# Group_12.net
KiCad netlist of a schematic drawn in EAGLE
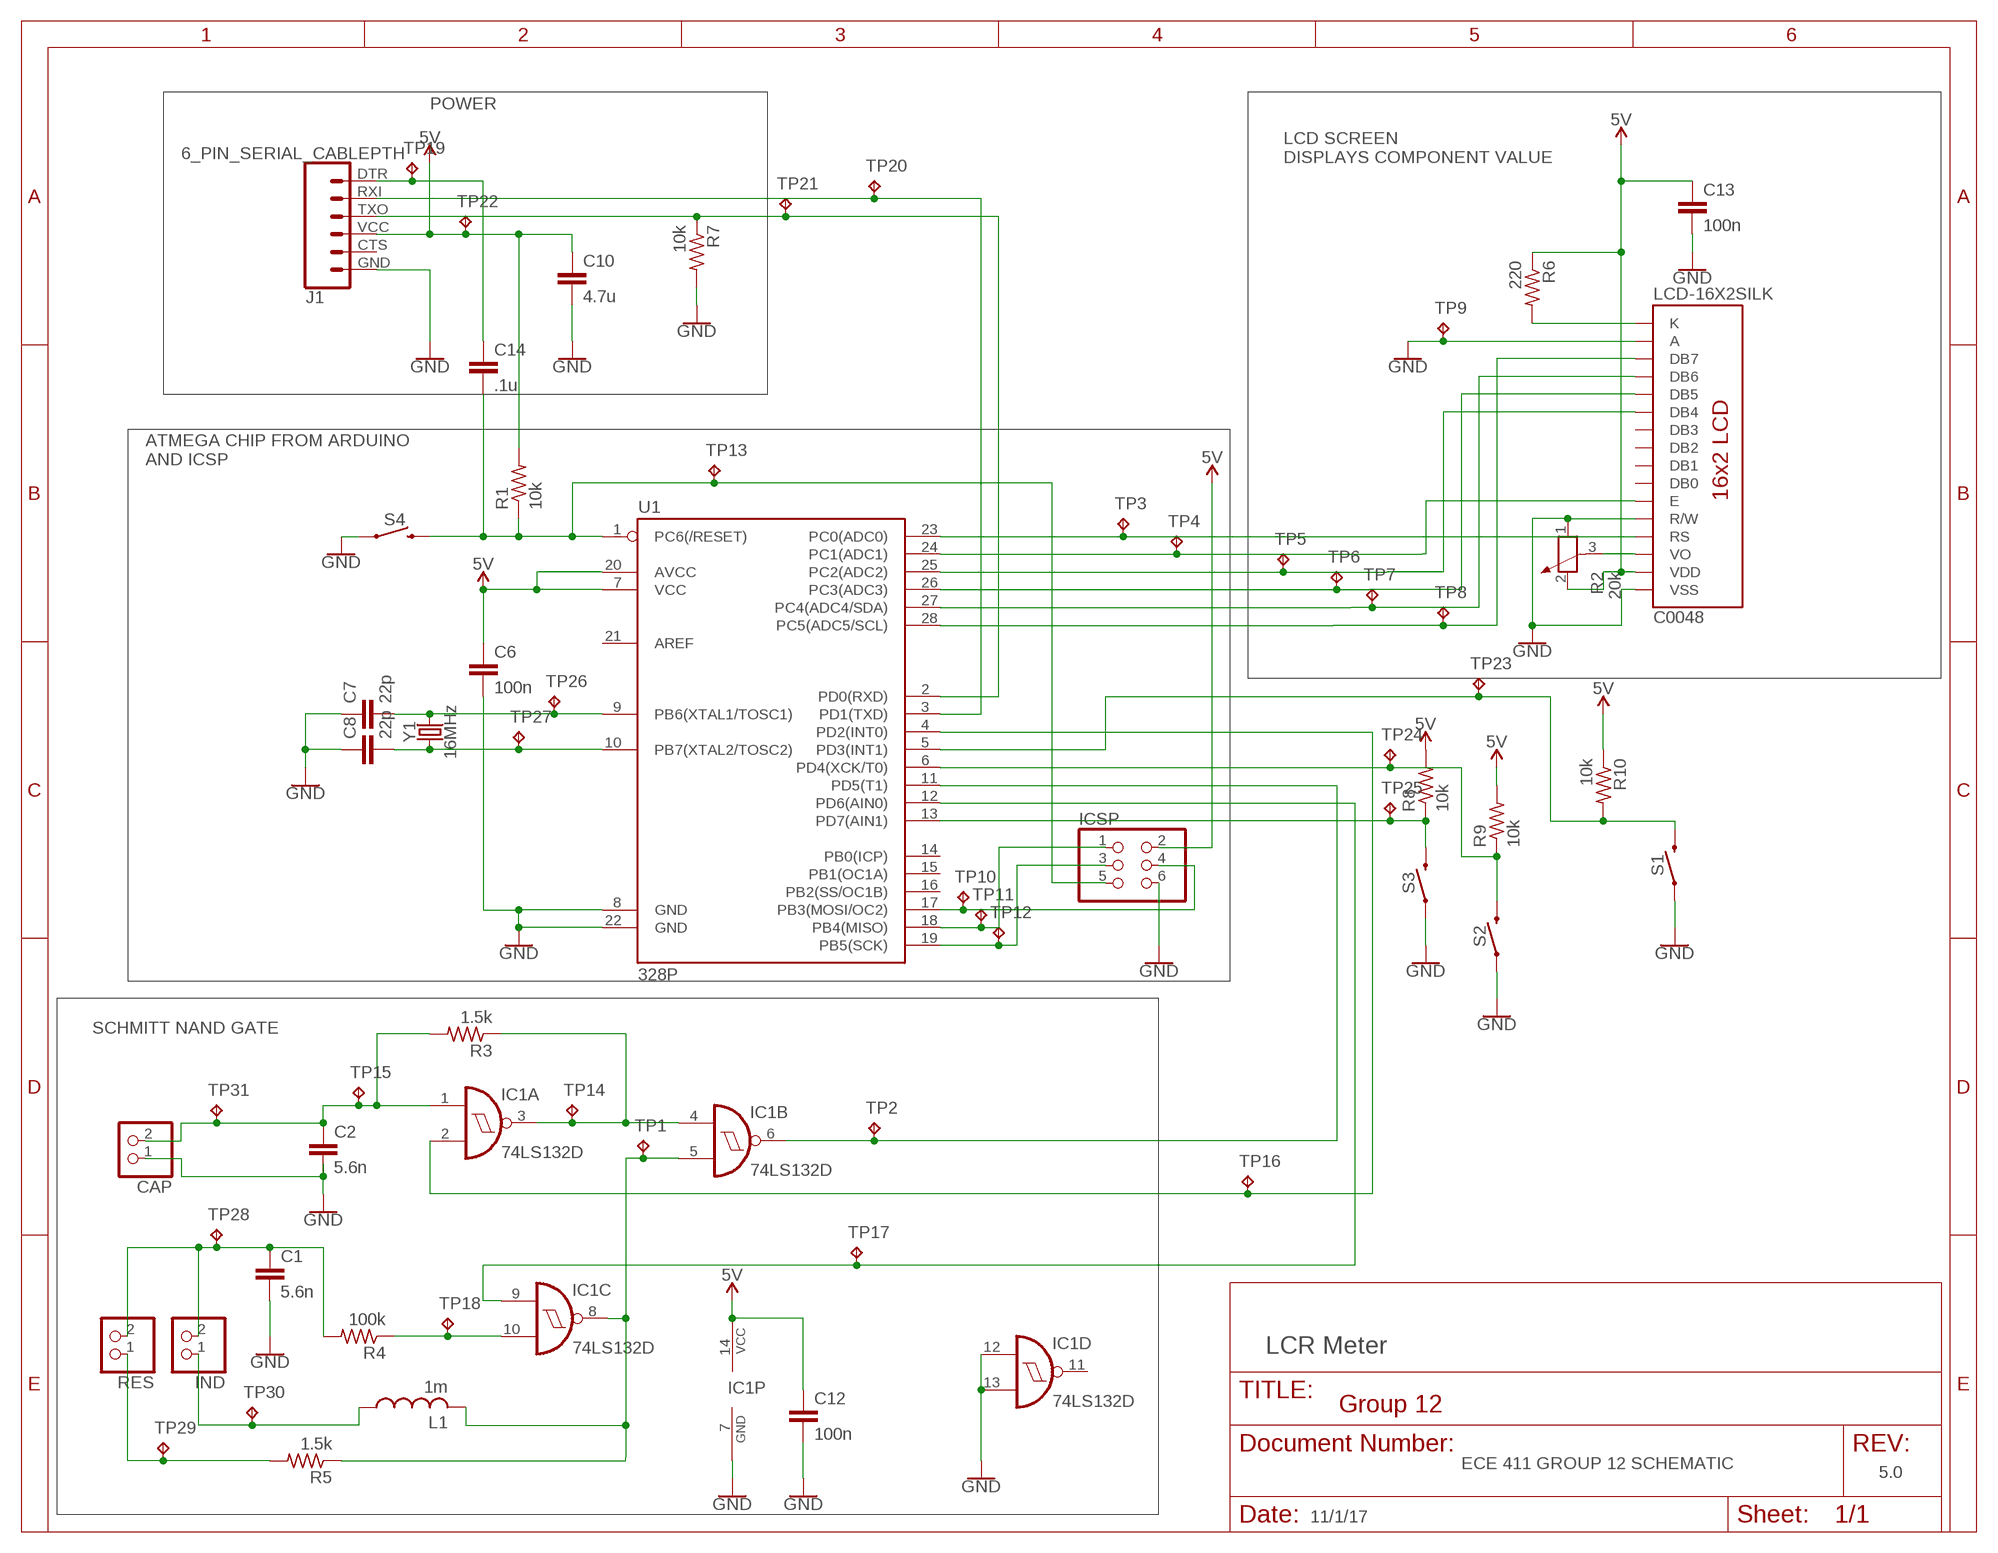
[diagram p0: schematic, sheet 1]

(export (version "E")
  (design (tool "Eeschema 10.0.6"))
  (components
    (comp (ref "C1")
      (value "5.6n")
      (footprint "eagle-import:C0805K")
      (libsource (lib "eagle-import") (part "C-EUC0805K"))
    )
    (comp (ref "C2")
      (value "5.6n")
      (footprint "eagle-import:C0805K")
      (libsource (lib "eagle-import") (part "C-EUC0805K"))
    )
    (comp (ref "C6")
      (value "100n")
      (footprint "eagle-import:C0805K")
      (libsource (lib "eagle-import") (part "C-EUC0805K"))
    )
    (comp (ref "C7")
      (value "22p")
      (footprint "eagle-import:C0805K")
      (libsource (lib "eagle-import") (part "C-EUC0805K"))
    )
    (comp (ref "C8")
      (value "22p")
      (footprint "eagle-import:C0805K")
      (libsource (lib "eagle-import") (part "C-EUC0805K"))
    )
    (comp (ref "C10")
      (value "4.7u")
      (footprint "eagle-import:C0805K")
      (libsource (lib "eagle-import") (part "C-EUC0805K"))
    )
    (comp (ref "C12")
      (value "100n")
      (footprint "eagle-import:C0805K")
      (libsource (lib "eagle-import") (part "C-EUC0805K"))
    )
    (comp (ref "C13")
      (value "100n")
      (footprint "eagle-import:C0805K")
      (libsource (lib "eagle-import") (part "C-EUC0805K"))
    )
    (comp (ref "C14")
      (value ".1u")
      (footprint "eagle-import:C0805K")
      (libsource (lib "eagle-import") (part "C-EUC0805K"))
    )
    (comp (ref "C0048")
      (value "LCD-16X2SILK")
      (footprint "eagle-import:LCD-16X2")
      (libsource (lib "eagle-import") (part "LCD-16X2SILK"))
    )
    (comp (ref "CAP")
      (value "PINHD-1X2")
      (footprint "eagle-import:1X02")
      (libsource (lib "eagle-import") (part "PINHD-1X2"))
    )
    (comp (ref "IC1")
      (value "74LS132D")
      (footprint "eagle-import:SO14")
      (libsource (lib "eagle-import") (part "74132DLS"))
    )
    (comp (ref "ICSP")
      (value "PINHD-2X3")
      (footprint "eagle-import:2X03")
      (libsource (lib "eagle-import") (part "PINHD-2X3"))
    )
    (comp (ref "IND")
      (value "PINHD-1X2")
      (footprint "eagle-import:1X02")
      (libsource (lib "eagle-import") (part "PINHD-1X2"))
    )
    (comp (ref "J1")
      (value "6_PIN_SERIAL_CABLEPTH")
      (footprint "eagle-import:FTDI_BASIC")
      (libsource (lib "eagle-import") (part "6_PIN_SERIAL_CABLEPTH"))
    )
    (comp (ref "L1")
      (value "1m")
      (footprint "eagle-import:0204_5")
      (libsource (lib "eagle-import") (part "L-US0204/5"))
    )
    (comp (ref "R1")
      (value "10k")
      (footprint "eagle-import:R0805")
      (libsource (lib "eagle-import") (part "R-US_R0805"))
    )
    (comp (ref "R2")
      (value "20k")
      (footprint "eagle-import:PT-10")
      (libsource (lib "eagle-import") (part "POTENTIOMETER_PT-10"))
    )
    (comp (ref "R3")
      (value "1.5k")
      (footprint "eagle-import:M0805")
      (libsource (lib "eagle-import") (part "R-US_M0805"))
    )
    (comp (ref "R4")
      (value "100k")
      (footprint "eagle-import:M0805")
      (libsource (lib "eagle-import") (part "R-US_M0805"))
    )
    (comp (ref "R5")
      (value "1.5k")
      (footprint "eagle-import:M0805")
      (libsource (lib "eagle-import") (part "R-US_M0805"))
    )
    (comp (ref "R6")
      (value "220")
      (footprint "eagle-import:R0805")
      (libsource (lib "eagle-import") (part "R-US_R0805"))
    )
    (comp (ref "R7")
      (value "10k")
      (footprint "eagle-import:R0805")
      (libsource (lib "eagle-import") (part "R-US_R0805"))
    )
    (comp (ref "R8")
      (value "10k")
      (footprint "eagle-import:R0805")
      (libsource (lib "eagle-import") (part "R-US_R0805"))
    )
    (comp (ref "R9")
      (value "10k")
      (footprint "eagle-import:R0805")
      (libsource (lib "eagle-import") (part "R-US_R0805"))
    )
    (comp (ref "R10")
      (value "10k")
      (footprint "eagle-import:R0805")
      (libsource (lib "eagle-import") (part "R-US_R0805"))
    )
    (comp (ref "RES")
      (value "PINHD-1X2")
      (footprint "eagle-import:1X02")
      (libsource (lib "eagle-import") (part "PINHD-1X2"))
    )
    (comp (ref "S1")
      (value "MOMENTARY-SWITCH-SPST-SMD-6.0X3.5MM")
      (footprint "eagle-import:TACTILE_SWITCH_SMD_6.0X3.5MM")
      (libsource (lib "eagle-import") (part "MOMENTARY-SWITCH-SPST-SMD-6.0X3.5MM"))
    )
    (comp (ref "S2")
      (value "MOMENTARY-SWITCH-SPST-SMD-6.0X3.5MM")
      (footprint "eagle-import:TACTILE_SWITCH_SMD_6.0X3.5MM")
      (libsource (lib "eagle-import") (part "MOMENTARY-SWITCH-SPST-SMD-6.0X3.5MM"))
    )
    (comp (ref "S3")
      (value "MOMENTARY-SWITCH-SPST-SMD-6.0X3.5MM")
      (footprint "eagle-import:TACTILE_SWITCH_SMD_6.0X3.5MM")
      (libsource (lib "eagle-import") (part "MOMENTARY-SWITCH-SPST-SMD-6.0X3.5MM"))
    )
    (comp (ref "S4")
      (value "MOMENTARY-SWITCH-SPST-SMD-6.0X3.5MM")
      (footprint "eagle-import:TACTILE_SWITCH_SMD_6.0X3.5MM")
      (libsource (lib "eagle-import") (part "MOMENTARY-SWITCH-SPST-SMD-6.0X3.5MM"))
    )
    (comp (ref "TP1")
      (value "TPPAD1-13")
      (footprint "eagle-import:P1-13")
      (libsource (lib "eagle-import") (part "TPPAD1-13"))
    )
    (comp (ref "TP2")
      (value "TPPAD1-13")
      (footprint "eagle-import:P1-13")
      (libsource (lib "eagle-import") (part "TPPAD1-13"))
    )
    (comp (ref "TP3")
      (value "TPPAD1-13")
      (footprint "eagle-import:P1-13")
      (libsource (lib "eagle-import") (part "TPPAD1-13"))
    )
    (comp (ref "TP4")
      (value "TPPAD1-13")
      (footprint "eagle-import:P1-13")
      (libsource (lib "eagle-import") (part "TPPAD1-13"))
    )
    (comp (ref "TP5")
      (value "TPPAD1-13")
      (footprint "eagle-import:P1-13")
      (libsource (lib "eagle-import") (part "TPPAD1-13"))
    )
    (comp (ref "TP6")
      (value "TPPAD1-13")
      (footprint "eagle-import:P1-13")
      (libsource (lib "eagle-import") (part "TPPAD1-13"))
    )
    (comp (ref "TP7")
      (value "TPPAD1-13")
      (footprint "eagle-import:P1-13")
      (libsource (lib "eagle-import") (part "TPPAD1-13"))
    )
    (comp (ref "TP8")
      (value "TPPAD1-13")
      (footprint "eagle-import:P1-13")
      (libsource (lib "eagle-import") (part "TPPAD1-13"))
    )
    (comp (ref "TP9")
      (value "TPPAD1-13")
      (footprint "eagle-import:P1-13")
      (libsource (lib "eagle-import") (part "TPPAD1-13"))
    )
    (comp (ref "TP10")
      (value "TPPAD1-13")
      (footprint "eagle-import:P1-13")
      (libsource (lib "eagle-import") (part "TPPAD1-13"))
    )
    (comp (ref "TP11")
      (value "TPPAD1-13")
      (footprint "eagle-import:P1-13")
      (libsource (lib "eagle-import") (part "TPPAD1-13"))
    )
    (comp (ref "TP12")
      (value "TPPAD1-13")
      (footprint "eagle-import:P1-13")
      (libsource (lib "eagle-import") (part "TPPAD1-13"))
    )
    (comp (ref "TP13")
      (value "TPPAD1-13")
      (footprint "eagle-import:P1-13")
      (libsource (lib "eagle-import") (part "TPPAD1-13"))
    )
    (comp (ref "TP14")
      (value "TPPAD1-13")
      (footprint "eagle-import:P1-13")
      (libsource (lib "eagle-import") (part "TPPAD1-13"))
    )
    (comp (ref "TP15")
      (value "TPPAD1-13")
      (footprint "eagle-import:P1-13")
      (libsource (lib "eagle-import") (part "TPPAD1-13"))
    )
    (comp (ref "TP16")
      (value "TPPAD1-13")
      (footprint "eagle-import:P1-13")
      (libsource (lib "eagle-import") (part "TPPAD1-13"))
    )
    (comp (ref "TP17")
      (value "TPPAD1-13")
      (footprint "eagle-import:P1-13")
      (libsource (lib "eagle-import") (part "TPPAD1-13"))
    )
    (comp (ref "TP18")
      (value "TPPAD1-13")
      (footprint "eagle-import:P1-13")
      (libsource (lib "eagle-import") (part "TPPAD1-13"))
    )
    (comp (ref "TP19")
      (value "TPPAD1-13")
      (footprint "eagle-import:P1-13")
      (libsource (lib "eagle-import") (part "TPPAD1-13"))
    )
    (comp (ref "TP20")
      (value "TPPAD1-13")
      (footprint "eagle-import:P1-13")
      (libsource (lib "eagle-import") (part "TPPAD1-13"))
    )
    (comp (ref "TP21")
      (value "TPPAD1-13")
      (footprint "eagle-import:P1-13")
      (libsource (lib "eagle-import") (part "TPPAD1-13"))
    )
    (comp (ref "TP22")
      (value "TPPAD1-13")
      (footprint "eagle-import:P1-13")
      (libsource (lib "eagle-import") (part "TPPAD1-13"))
    )
    (comp (ref "TP23")
      (value "TPPAD1-13")
      (footprint "eagle-import:P1-13")
      (libsource (lib "eagle-import") (part "TPPAD1-13"))
    )
    (comp (ref "TP24")
      (value "TPPAD1-13")
      (footprint "eagle-import:P1-13")
      (libsource (lib "eagle-import") (part "TPPAD1-13"))
    )
    (comp (ref "TP25")
      (value "TPPAD1-13")
      (footprint "eagle-import:P1-13")
      (libsource (lib "eagle-import") (part "TPPAD1-13"))
    )
    (comp (ref "TP26")
      (value "TPPAD1-13")
      (footprint "eagle-import:P1-13")
      (libsource (lib "eagle-import") (part "TPPAD1-13"))
    )
    (comp (ref "TP27")
      (value "TPPAD1-13")
      (footprint "eagle-import:P1-13")
      (libsource (lib "eagle-import") (part "TPPAD1-13"))
    )
    (comp (ref "TP28")
      (value "TPPAD1-13")
      (footprint "eagle-import:P1-13")
      (libsource (lib "eagle-import") (part "TPPAD1-13"))
    )
    (comp (ref "TP29")
      (value "TPPAD1-13")
      (footprint "eagle-import:P1-13")
      (libsource (lib "eagle-import") (part "TPPAD1-13"))
    )
    (comp (ref "TP30")
      (value "TPPAD1-13")
      (footprint "eagle-import:P1-13")
      (libsource (lib "eagle-import") (part "TPPAD1-13"))
    )
    (comp (ref "TP31")
      (value "TPPAD1-13")
      (footprint "eagle-import:P1-13")
      (libsource (lib "eagle-import") (part "TPPAD1-13"))
    )
    (comp (ref "U1")
      (value "328P")
      (footprint "eagle-import:DIP28")
      (libsource (lib "eagle-import") (part "ATMEGA328P_PDIP"))
    )
    (comp (ref "Y1")
      (value "16MHz")
      (footprint "eagle-import:CRYSTAL-SMD-5X3.2-4PAD")
      (libsource (lib "eagle-import") (part "CRYSTAL-16MHZSMD-5X3.2"))
    )
  )
  (nets
    (net (code "1") (name "5V") (class "Default")
      (node (ref "C0048") (pin "2") (pinfunction "VDD_2") (pintype "power_in"))
      (node (ref "C10") (pin "1") (pinfunction "1_1") (pintype "passive"))
      (node (ref "C12") (pin "1") (pinfunction "1_1") (pintype "passive"))
      (node (ref "C13") (pin "1") (pinfunction "1_1") (pintype "passive"))
      (node (ref "C6") (pin "1") (pinfunction "1_1") (pintype "passive"))
      (node (ref "IC1") (pin "14") (pinfunction "VCC_14") (pintype "power_in"))
      (node (ref "ICSP") (pin "2") (pinfunction "2_2") (pintype "passive"))
      (node (ref "J1") (pin "VCC") (pinfunction "4_VCC") (pintype "passive"))
      (node (ref "R1") (pin "2") (pinfunction "2_2") (pintype "passive"))
      (node (ref "R10") (pin "1") (pinfunction "1_1") (pintype "passive"))
      (node (ref "R2") (pin "2") (pinfunction "2_2") (pintype "passive"))
      (node (ref "R6") (pin "1") (pinfunction "1_1") (pintype "passive"))
      (node (ref "R8") (pin "2") (pinfunction "2_2") (pintype "passive"))
      (node (ref "R9") (pin "2") (pinfunction "2_2") (pintype "passive"))
      (node (ref "TP22") (pin "TP") (pinfunction "TP_TP") (pintype "input"))
      (node (ref "U1") (pin "20") (pinfunction "AVCC_20") (pintype "bidirectional"))
      (node (ref "U1") (pin "7") (pinfunction "VCC_7") (pintype "bidirectional"))
    )
    (net (code "2") (name "GND") (class "Default")
      (node (ref "C0048") (pin "1") (pinfunction "VSS_1") (pintype "power_in"))
      (node (ref "C0048") (pin "15") (pinfunction "A_15") (pintype "power_in"))
      (node (ref "C0048") (pin "5") (pinfunction "R/W_5") (pintype "input"))
      (node (ref "C1") (pin "2") (pinfunction "2_2") (pintype "passive"))
      (node (ref "C10") (pin "2") (pinfunction "2_2") (pintype "passive"))
      (node (ref "C12") (pin "2") (pinfunction "2_2") (pintype "passive"))
      (node (ref "C13") (pin "2") (pinfunction "2_2") (pintype "passive"))
      (node (ref "C2") (pin "2") (pinfunction "2_2") (pintype "passive"))
      (node (ref "C6") (pin "2") (pinfunction "2_2") (pintype "passive"))
      (node (ref "C7") (pin "1") (pinfunction "1_1") (pintype "passive"))
      (node (ref "C8") (pin "1") (pinfunction "1_1") (pintype "passive"))
      (node (ref "CAP") (pin "1") (pinfunction "1_1") (pintype "passive"))
      (node (ref "IC1") (pin "12") (pinfunction "I0_12") (pintype "input"))
      (node (ref "IC1") (pin "13") (pinfunction "I1_13") (pintype "input"))
      (node (ref "IC1") (pin "7") (pinfunction "GND_7") (pintype "power_in"))
      (node (ref "ICSP") (pin "6") (pinfunction "6_6") (pintype "passive"))
      (node (ref "J1") (pin "GND") (pinfunction "6_GND") (pintype "passive"))
      (node (ref "R2") (pin "1") (pinfunction "1_1") (pintype "passive"))
      (node (ref "R7") (pin "2") (pinfunction "2_2") (pintype "passive"))
      (node (ref "S1") (pin "1") (pinfunction "1_1") (pintype "passive"))
      (node (ref "S2") (pin "1") (pinfunction "1_1") (pintype "passive"))
      (node (ref "S3") (pin "1") (pinfunction "1_1") (pintype "passive"))
      (node (ref "S4") (pin "1") (pinfunction "1_1") (pintype "passive"))
      (node (ref "TP9") (pin "TP") (pinfunction "TP_TP") (pintype "input"))
      (node (ref "U1") (pin "22") (pinfunction "GND_22") (pintype "bidirectional"))
      (node (ref "U1") (pin "8") (pinfunction "GND_8") (pintype "bidirectional"))
    )
    (net (code "3") (name "Net-(C1-Pad1)") (class "Default")
      (node (ref "C1") (pin "1") (pinfunction "1_1") (pintype "passive"))
      (node (ref "IND") (pin "2") (pinfunction "2_2") (pintype "passive"))
      (node (ref "R4") (pin "2") (pinfunction "2_2") (pintype "passive"))
      (node (ref "RES") (pin "2") (pinfunction "2_2") (pintype "passive"))
      (node (ref "TP28") (pin "TP") (pinfunction "TP_TP") (pintype "input"))
    )
    (net (code "4") (name "Net-(C0048-DB4)") (class "Default")
      (node (ref "C0048") (pin "11") (pinfunction "DB4_11") (pintype "bidirectional"))
      (node (ref "TP5") (pin "TP") (pinfunction "TP_TP") (pintype "input"))
      (node (ref "U1") (pin "25") (pinfunction "PC2(ADC2)_25") (pintype "bidirectional"))
    )
    (net (code "5") (name "Net-(C0048-DB5)") (class "Default")
      (node (ref "C0048") (pin "12") (pinfunction "DB5_12") (pintype "bidirectional"))
      (node (ref "TP6") (pin "TP") (pinfunction "TP_TP") (pintype "input"))
      (node (ref "U1") (pin "26") (pinfunction "PC3(ADC3)_26") (pintype "bidirectional"))
    )
    (net (code "6") (name "Net-(C0048-DB6)") (class "Default")
      (node (ref "C0048") (pin "13") (pinfunction "DB6_13") (pintype "bidirectional"))
      (node (ref "TP7") (pin "TP") (pinfunction "TP_TP") (pintype "input"))
      (node (ref "U1") (pin "27") (pinfunction "PC4(ADC4/SDA)_27") (pintype "bidirectional"))
    )
    (net (code "7") (name "Net-(C0048-DB7)") (class "Default")
      (node (ref "C0048") (pin "14") (pinfunction "DB7_14") (pintype "bidirectional"))
      (node (ref "TP8") (pin "TP") (pinfunction "TP_TP") (pintype "input"))
      (node (ref "U1") (pin "28") (pinfunction "PC5(ADC5/SCL)_28") (pintype "bidirectional"))
    )
    (net (code "8") (name "Net-(C0048-E)") (class "Default")
      (node (ref "C0048") (pin "6") (pinfunction "E_6") (pintype "input"))
      (node (ref "TP4") (pin "TP") (pinfunction "TP_TP") (pintype "input"))
      (node (ref "U1") (pin "24") (pinfunction "PC1(ADC1)_24") (pintype "bidirectional"))
    )
    (net (code "9") (name "Net-(C0048-K)") (class "Default")
      (node (ref "C0048") (pin "16") (pinfunction "K_16") (pintype "power_in"))
      (node (ref "R6") (pin "2") (pinfunction "2_2") (pintype "passive"))
    )
    (net (code "10") (name "Net-(C0048-RS)") (class "Default")
      (node (ref "C0048") (pin "4") (pinfunction "RS_4") (pintype "input"))
      (node (ref "TP3") (pin "TP") (pinfunction "TP_TP") (pintype "input"))
      (node (ref "U1") (pin "23") (pinfunction "PC0(ADC0)_23") (pintype "bidirectional"))
    )
    (net (code "11") (name "Net-(C0048-VO)") (class "Default")
      (node (ref "C0048") (pin "3") (pinfunction "VO_3") (pintype "bidirectional"))
      (node (ref "R2") (pin "3") (pinfunction "3_3") (pintype "passive"))
    )
    (net (code "12") (name "Net-(IC1A-I0)") (class "Default")
      (node (ref "C2") (pin "1") (pinfunction "1_1") (pintype "passive"))
      (node (ref "CAP") (pin "2") (pinfunction "2_2") (pintype "passive"))
      (node (ref "IC1") (pin "1") (pinfunction "I0_1") (pintype "input"))
      (node (ref "R3") (pin "2") (pinfunction "2_2") (pintype "passive"))
      (node (ref "TP15") (pin "TP") (pinfunction "TP_TP") (pintype "input"))
      (node (ref "TP31") (pin "TP") (pinfunction "TP_TP") (pintype "input"))
    )
    (net (code "13") (name "Net-(IC1A-I1)") (class "Default")
      (node (ref "IC1") (pin "2") (pinfunction "I1_2") (pintype "input"))
      (node (ref "TP16") (pin "TP") (pinfunction "TP_TP") (pintype "input"))
      (node (ref "U1") (pin "4") (pinfunction "PD2(INT0)_4") (pintype "bidirectional"))
    )
    (net (code "14") (name "Net-(IC1A-O)") (class "Default")
      (node (ref "IC1") (pin "3") (pinfunction "O_3") (pintype "output"))
      (node (ref "IC1") (pin "4") (pinfunction "I0_4") (pintype "input"))
      (node (ref "R3") (pin "1") (pinfunction "1_1") (pintype "passive"))
      (node (ref "TP14") (pin "TP") (pinfunction "TP_TP") (pintype "input"))
    )
    (net (code "15") (name "Net-(IC1B-I1)") (class "Default")
      (node (ref "IC1") (pin "5") (pinfunction "I1_5") (pintype "input"))
      (node (ref "IC1") (pin "8") (pinfunction "O_8") (pintype "output"))
      (node (ref "L1") (pin "2") (pinfunction "2_2") (pintype "passive"))
      (node (ref "R5") (pin "1") (pinfunction "1_1") (pintype "passive"))
      (node (ref "TP1") (pin "TP") (pinfunction "TP_TP") (pintype "input"))
    )
    (net (code "16") (name "Net-(IC1B-O)") (class "Default")
      (node (ref "IC1") (pin "6") (pinfunction "O_6") (pintype "output"))
      (node (ref "TP2") (pin "TP") (pinfunction "TP_TP") (pintype "input"))
      (node (ref "U1") (pin "11") (pinfunction "PD5(T1)_11") (pintype "bidirectional"))
    )
    (net (code "17") (name "Net-(IC1C-I0)") (class "Default")
      (node (ref "IC1") (pin "9") (pinfunction "I0_9") (pintype "input"))
      (node (ref "TP17") (pin "TP") (pinfunction "TP_TP") (pintype "input"))
      (node (ref "U1") (pin "12") (pinfunction "PD6(AIN0)_12") (pintype "bidirectional"))
    )
    (net (code "18") (name "Net-(IC1C-I1)") (class "Default")
      (node (ref "IC1") (pin "10") (pinfunction "I1_10") (pintype "input"))
      (node (ref "R4") (pin "1") (pinfunction "1_1") (pintype "passive"))
      (node (ref "TP18") (pin "TP") (pinfunction "TP_TP") (pintype "input"))
    )
    (net (code "19") (name "Net-(IND-Pad1)") (class "Default")
      (node (ref "IND") (pin "1") (pinfunction "1_1") (pintype "passive"))
      (node (ref "L1") (pin "1") (pinfunction "1_1") (pintype "passive"))
      (node (ref "TP30") (pin "TP") (pinfunction "TP_TP") (pintype "input"))
    )
    (net (code "20") (name "Net-(J1-1)") (class "Default")
      (node (ref "C14") (pin "1") (pinfunction "1_1") (pintype "passive"))
      (node (ref "J1") (pin "DTR") (pinfunction "1_DTR") (pintype "passive"))
      (node (ref "TP19") (pin "TP") (pinfunction "TP_TP") (pintype "input"))
    )
    (net (code "21") (name "Net-(J1-2)") (class "Default")
      (node (ref "J1") (pin "RXI") (pinfunction "2_RXI") (pintype "passive"))
      (node (ref "TP20") (pin "TP") (pinfunction "TP_TP") (pintype "input"))
      (node (ref "U1") (pin "3") (pinfunction "PD1(TXD)_3") (pintype "bidirectional"))
    )
    (net (code "22") (name "Net-(J1-3)") (class "Default")
      (node (ref "J1") (pin "TXO") (pinfunction "3_TXO") (pintype "passive"))
      (node (ref "R7") (pin "1") (pinfunction "1_1") (pintype "passive"))
      (node (ref "TP21") (pin "TP") (pinfunction "TP_TP") (pintype "input"))
      (node (ref "U1") (pin "2") (pinfunction "PD0(RXD)_2") (pintype "bidirectional"))
    )
    (net (code "23") (name "Net-(R5-Pad2)") (class "Default")
      (node (ref "R5") (pin "2") (pinfunction "2_2") (pintype "passive"))
      (node (ref "RES") (pin "1") (pinfunction "1_1") (pintype "passive"))
      (node (ref "TP29") (pin "TP") (pinfunction "TP_TP") (pintype "input"))
    )
    (net (code "24") (name "Net-(U1-PB3(MOSI{slash}OC2))") (class "Default")
      (node (ref "ICSP") (pin "4") (pinfunction "4_4") (pintype "passive"))
      (node (ref "TP10") (pin "TP") (pinfunction "TP_TP") (pintype "input"))
      (node (ref "U1") (pin "17") (pinfunction "PB3(MOSI/OC2)_17") (pintype "bidirectional"))
    )
    (net (code "25") (name "Net-(U1-PB4(MISO))") (class "Default")
      (node (ref "ICSP") (pin "1") (pinfunction "1_1") (pintype "passive"))
      (node (ref "TP11") (pin "TP") (pinfunction "TP_TP") (pintype "input"))
      (node (ref "U1") (pin "18") (pinfunction "PB4(MISO)_18") (pintype "bidirectional"))
    )
    (net (code "26") (name "Net-(U1-PB5(SCK))") (class "Default")
      (node (ref "ICSP") (pin "3") (pinfunction "3_3") (pintype "passive"))
      (node (ref "TP12") (pin "TP") (pinfunction "TP_TP") (pintype "input"))
      (node (ref "U1") (pin "19") (pinfunction "PB5(SCK)_19") (pintype "bidirectional"))
    )
    (net (code "27") (name "Net-(U1-PB6(XTAL1{slash}TOSC1))") (class "Default")
      (node (ref "C7") (pin "2") (pinfunction "2_2") (pintype "passive"))
      (node (ref "TP26") (pin "TP") (pinfunction "TP_TP") (pintype "input"))
      (node (ref "U1") (pin "9") (pinfunction "PB6(XTAL1/TOSC1)_9") (pintype "bidirectional"))
      (node (ref "Y1") (pin "3") (pinfunction "2_3") (pintype "passive"))
    )
    (net (code "28") (name "Net-(U1-PB7(XTAL2{slash}TOSC2))") (class "Default")
      (node (ref "C8") (pin "2") (pinfunction "2_2") (pintype "passive"))
      (node (ref "TP27") (pin "TP") (pinfunction "TP_TP") (pintype "input"))
      (node (ref "U1") (pin "10") (pinfunction "PB7(XTAL2/TOSC2)_10") (pintype "bidirectional"))
      (node (ref "Y1") (pin "1") (pinfunction "1_1") (pintype "passive"))
    )
    (net (code "29") (name "Net-(U1-PC6({slash}RESET))") (class "Default")
      (node (ref "C14") (pin "2") (pinfunction "2_2") (pintype "passive"))
      (node (ref "ICSP") (pin "5") (pinfunction "5_5") (pintype "passive"))
      (node (ref "R1") (pin "1") (pinfunction "1_1") (pintype "passive"))
      (node (ref "S4") (pin "2") (pinfunction "2_2") (pintype "passive"))
      (node (ref "TP13") (pin "TP") (pinfunction "TP_TP") (pintype "input"))
      (node (ref "U1") (pin "1") (pinfunction "PC6(/RESET)_1") (pintype "bidirectional"))
    )
    (net (code "30") (name "Net-(U1-PD3(INT1))") (class "Default")
      (node (ref "R10") (pin "2") (pinfunction "2_2") (pintype "passive"))
      (node (ref "S1") (pin "2") (pinfunction "2_2") (pintype "passive"))
      (node (ref "TP23") (pin "TP") (pinfunction "TP_TP") (pintype "input"))
      (node (ref "U1") (pin "5") (pinfunction "PD3(INT1)_5") (pintype "bidirectional"))
    )
    (net (code "31") (name "Net-(U1-PD4(XCK{slash}T0))") (class "Default")
      (node (ref "R9") (pin "1") (pinfunction "1_1") (pintype "passive"))
      (node (ref "S2") (pin "2") (pinfunction "2_2") (pintype "passive"))
      (node (ref "TP24") (pin "TP") (pinfunction "TP_TP") (pintype "input"))
      (node (ref "U1") (pin "6") (pinfunction "PD4(XCK/T0)_6") (pintype "bidirectional"))
    )
    (net (code "32") (name "Net-(U1-PD7(AIN1))") (class "Default")
      (node (ref "R8") (pin "1") (pinfunction "1_1") (pintype "passive"))
      (node (ref "S3") (pin "2") (pinfunction "2_2") (pintype "passive"))
      (node (ref "TP25") (pin "TP") (pinfunction "TP_TP") (pintype "input"))
      (node (ref "U1") (pin "13") (pinfunction "PD7(AIN1)_13") (pintype "bidirectional"))
    )
    (net (code "33") (name "unconnected-(C0048-DB0-Pad7)") (class "Default")
      (node (ref "C0048") (pin "7") (pinfunction "DB0_7") (pintype "bidirectional"))
    )
    (net (code "34") (name "unconnected-(C0048-DB1-Pad8)") (class "Default")
      (node (ref "C0048") (pin "8") (pinfunction "DB1_8") (pintype "bidirectional"))
    )
    (net (code "35") (name "unconnected-(C0048-DB2-Pad9)") (class "Default")
      (node (ref "C0048") (pin "9") (pinfunction "DB2_9") (pintype "bidirectional"))
    )
    (net (code "36") (name "unconnected-(C0048-DB3-Pad10)") (class "Default")
      (node (ref "C0048") (pin "10") (pinfunction "DB3_10") (pintype "bidirectional"))
    )
    (net (code "37") (name "unconnected-(IC1D-O-Pad11)") (class "Default")
      (node (ref "IC1") (pin "11") (pinfunction "O_11") (pintype "output"))
    )
    (net (code "38") (name "unconnected-(J1-5-PadCTS)") (class "Default")
      (node (ref "J1") (pin "CTS") (pinfunction "5_CTS") (pintype "passive"))
    )
    (net (code "39") (name "unconnected-(U1-AREF-Pad21)") (class "Default")
      (node (ref "U1") (pin "21") (pinfunction "AREF_21") (pintype "bidirectional"))
    )
    (net (code "40") (name "unconnected-(U1-PB0(ICP)-Pad14)") (class "Default")
      (node (ref "U1") (pin "14") (pinfunction "PB0(ICP)_14") (pintype "bidirectional"))
    )
    (net (code "41") (name "unconnected-(U1-PB1(OC1A)-Pad15)") (class "Default")
      (node (ref "U1") (pin "15") (pinfunction "PB1(OC1A)_15") (pintype "bidirectional"))
    )
    (net (code "42") (name "unconnected-(U1-PB2(SS{slash}OC1B)-Pad16)") (class "Default")
      (node (ref "U1") (pin "16") (pinfunction "PB2(SS/OC1B)_16") (pintype "bidirectional"))
    )
  )
)
